# katzenlaserturret.net
KiCad netlist of a schematic drawn in EAGLE
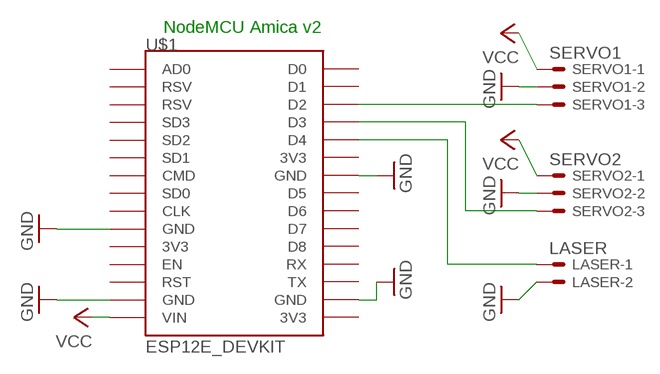
[diagram p0: schematic, sheet 1]

(export (version "E")
  (design (tool "Eeschema 10.0.6"))
  (components
    (comp (ref "LASER")
      (value "LASER")
      (footprint "eagle-import:22-23-2021")
      (fields (field (name "MF") "MOLEX") (field (name "MPN") "22-23-2021"))
      (libsource (lib "eagle-import") (part "22-23-2021"))
    )
    (comp (ref "SERVO1")
      (value "SERVO1")
      (footprint "eagle-import:22-23-2031")
      (fields (field (name "MF") "MOLEX") (field (name "MPN") "22-23-2031"))
      (libsource (lib "eagle-import") (part "22-23-2031"))
    )
    (comp (ref "SERVO2")
      (value "SERVO2")
      (footprint "eagle-import:22-23-2031")
      (fields (field (name "MF") "MOLEX") (field (name "MPN") "22-23-2031"))
      (libsource (lib "eagle-import") (part "22-23-2031"))
    )
    (comp (ref "U$1")
      (value "ESP12E_DEVKIT")
      (footprint "eagle-import:ESP12E_DEVKIT")
      (libsource (lib "eagle-import") (part "ESP12E_DEVKIT"))
    )
  )
  (nets
    (net (code "1") (name "GND") (class "Default")
      (node (ref "LASER") (pin "2") (pinfunction "S_2") (pintype "passive"))
      (node (ref "SERVO1") (pin "2") (pinfunction "S_2") (pintype "passive"))
      (node (ref "SERVO2") (pin "2") (pinfunction "S_2") (pintype "passive"))
      (node (ref "U$1") (pin "GND@0") (pinfunction "GND_GND@0") (pintype "bidirectional"))
      (node (ref "U$1") (pin "GND@1") (pinfunction "GND_GND@1") (pintype "bidirectional"))
      (node (ref "U$1") (pin "GND@2") (pinfunction "GND_GND@2") (pintype "bidirectional"))
      (node (ref "U$1") (pin "GND@3") (pinfunction "GND_GND@3") (pintype "bidirectional"))
    )
    (net (code "2") (name "Net-(LASERA-S)") (class "Default")
      (node (ref "LASER") (pin "1") (pinfunction "S_1") (pintype "passive"))
      (node (ref "U$1") (pin "D4") (pinfunction "D4_D4") (pintype "bidirectional"))
    )
    (net (code "3") (name "Net-(SERVO1C-S)") (class "Default")
      (node (ref "SERVO1") (pin "3") (pinfunction "S_3") (pintype "passive"))
      (node (ref "U$1") (pin "D2") (pinfunction "D2_D2") (pintype "bidirectional"))
    )
    (net (code "4") (name "Net-(SERVO2C-S)") (class "Default")
      (node (ref "SERVO2") (pin "3") (pinfunction "S_3") (pintype "passive"))
      (node (ref "U$1") (pin "D3") (pinfunction "D3_D3") (pintype "bidirectional"))
    )
    (net (code "5") (name "VCC") (class "Default")
      (node (ref "SERVO1") (pin "1") (pinfunction "S_1") (pintype "passive"))
      (node (ref "SERVO2") (pin "1") (pinfunction "S_1") (pintype "passive"))
      (node (ref "U$1") (pin "VIN") (pinfunction "VIN_VIN") (pintype "bidirectional"))
    )
    (net (code "6") (name "unconnected-(U$1-3V3-Pad3V3@0)") (class "Default")
      (node (ref "U$1") (pin "3V3@0") (pinfunction "3V3_3V3@0") (pintype "bidirectional"))
    )
    (net (code "7") (name "unconnected-(U$1-3V3-Pad3V3@1)") (class "Default")
      (node (ref "U$1") (pin "3V3@1") (pinfunction "3V3_3V3@1") (pintype "bidirectional"))
    )
    (net (code "8") (name "unconnected-(U$1-3V3-Pad3V3@2)") (class "Default")
      (node (ref "U$1") (pin "3V3@2") (pinfunction "3V3_3V3@2") (pintype "bidirectional"))
    )
    (net (code "9") (name "unconnected-(U$1-PadAD0)") (class "Default")
      (node (ref "U$1") (pin "AD0") (pinfunction "AD0_AD0") (pintype "bidirectional"))
    )
    (net (code "10") (name "unconnected-(U$1-PadCLK)") (class "Default")
      (node (ref "U$1") (pin "CLK") (pinfunction "CLK_CLK") (pintype "bidirectional"))
    )
    (net (code "11") (name "unconnected-(U$1-PadCMD)") (class "Default")
      (node (ref "U$1") (pin "CMD") (pinfunction "CMD_CMD") (pintype "bidirectional"))
    )
    (net (code "12") (name "unconnected-(U$1-PadD0)") (class "Default")
      (node (ref "U$1") (pin "D0") (pinfunction "D0_D0") (pintype "bidirectional"))
    )
    (net (code "13") (name "unconnected-(U$1-PadD1)") (class "Default")
      (node (ref "U$1") (pin "D1") (pinfunction "D1_D1") (pintype "bidirectional"))
    )
    (net (code "14") (name "unconnected-(U$1-PadD5)") (class "Default")
      (node (ref "U$1") (pin "D5") (pinfunction "D5_D5") (pintype "bidirectional"))
    )
    (net (code "15") (name "unconnected-(U$1-PadD6)") (class "Default")
      (node (ref "U$1") (pin "D6") (pinfunction "D6_D6") (pintype "bidirectional"))
    )
    (net (code "16") (name "unconnected-(U$1-PadD7)") (class "Default")
      (node (ref "U$1") (pin "D7") (pinfunction "D7_D7") (pintype "bidirectional"))
    )
    (net (code "17") (name "unconnected-(U$1-PadD8)") (class "Default")
      (node (ref "U$1") (pin "D8") (pinfunction "D8_D8") (pintype "bidirectional"))
    )
    (net (code "18") (name "unconnected-(U$1-PadEN)") (class "Default")
      (node (ref "U$1") (pin "EN") (pinfunction "EN_EN") (pintype "bidirectional"))
    )
    (net (code "19") (name "unconnected-(U$1-PadRST)") (class "Default")
      (node (ref "U$1") (pin "RST") (pinfunction "RST_RST") (pintype "bidirectional"))
    )
    (net (code "20") (name "unconnected-(U$1-PadRX)") (class "Default")
      (node (ref "U$1") (pin "RX") (pinfunction "RX_RX") (pintype "bidirectional"))
    )
    (net (code "21") (name "unconnected-(U$1-PadSD0)") (class "Default")
      (node (ref "U$1") (pin "SD0") (pinfunction "SD0_SD0") (pintype "bidirectional"))
    )
    (net (code "22") (name "unconnected-(U$1-PadSD1)") (class "Default")
      (node (ref "U$1") (pin "SD1") (pinfunction "SD1_SD1") (pintype "bidirectional"))
    )
    (net (code "23") (name "unconnected-(U$1-PadSD2)") (class "Default")
      (node (ref "U$1") (pin "SD2") (pinfunction "SD2_SD2") (pintype "bidirectional"))
    )
    (net (code "24") (name "unconnected-(U$1-PadSD3)") (class "Default")
      (node (ref "U$1") (pin "SD3") (pinfunction "SD3_SD3") (pintype "bidirectional"))
    )
    (net (code "25") (name "unconnected-(U$1-PadTX)") (class "Default")
      (node (ref "U$1") (pin "TX") (pinfunction "TX_TX") (pintype "bidirectional"))
    )
    (net (code "26") (name "unconnected-(U$1-RSV-PadRSV@0)") (class "Default")
      (node (ref "U$1") (pin "RSV@0") (pinfunction "RSV_RSV@0") (pintype "bidirectional"))
    )
    (net (code "27") (name "unconnected-(U$1-RSV-PadRSV@1)") (class "Default")
      (node (ref "U$1") (pin "RSV@1") (pinfunction "RSV_RSV@1") (pintype "bidirectional"))
    )
  )
)
